# PSM_components_REV_C.net
KiCad netlist of a schematic drawn in Altium Designer
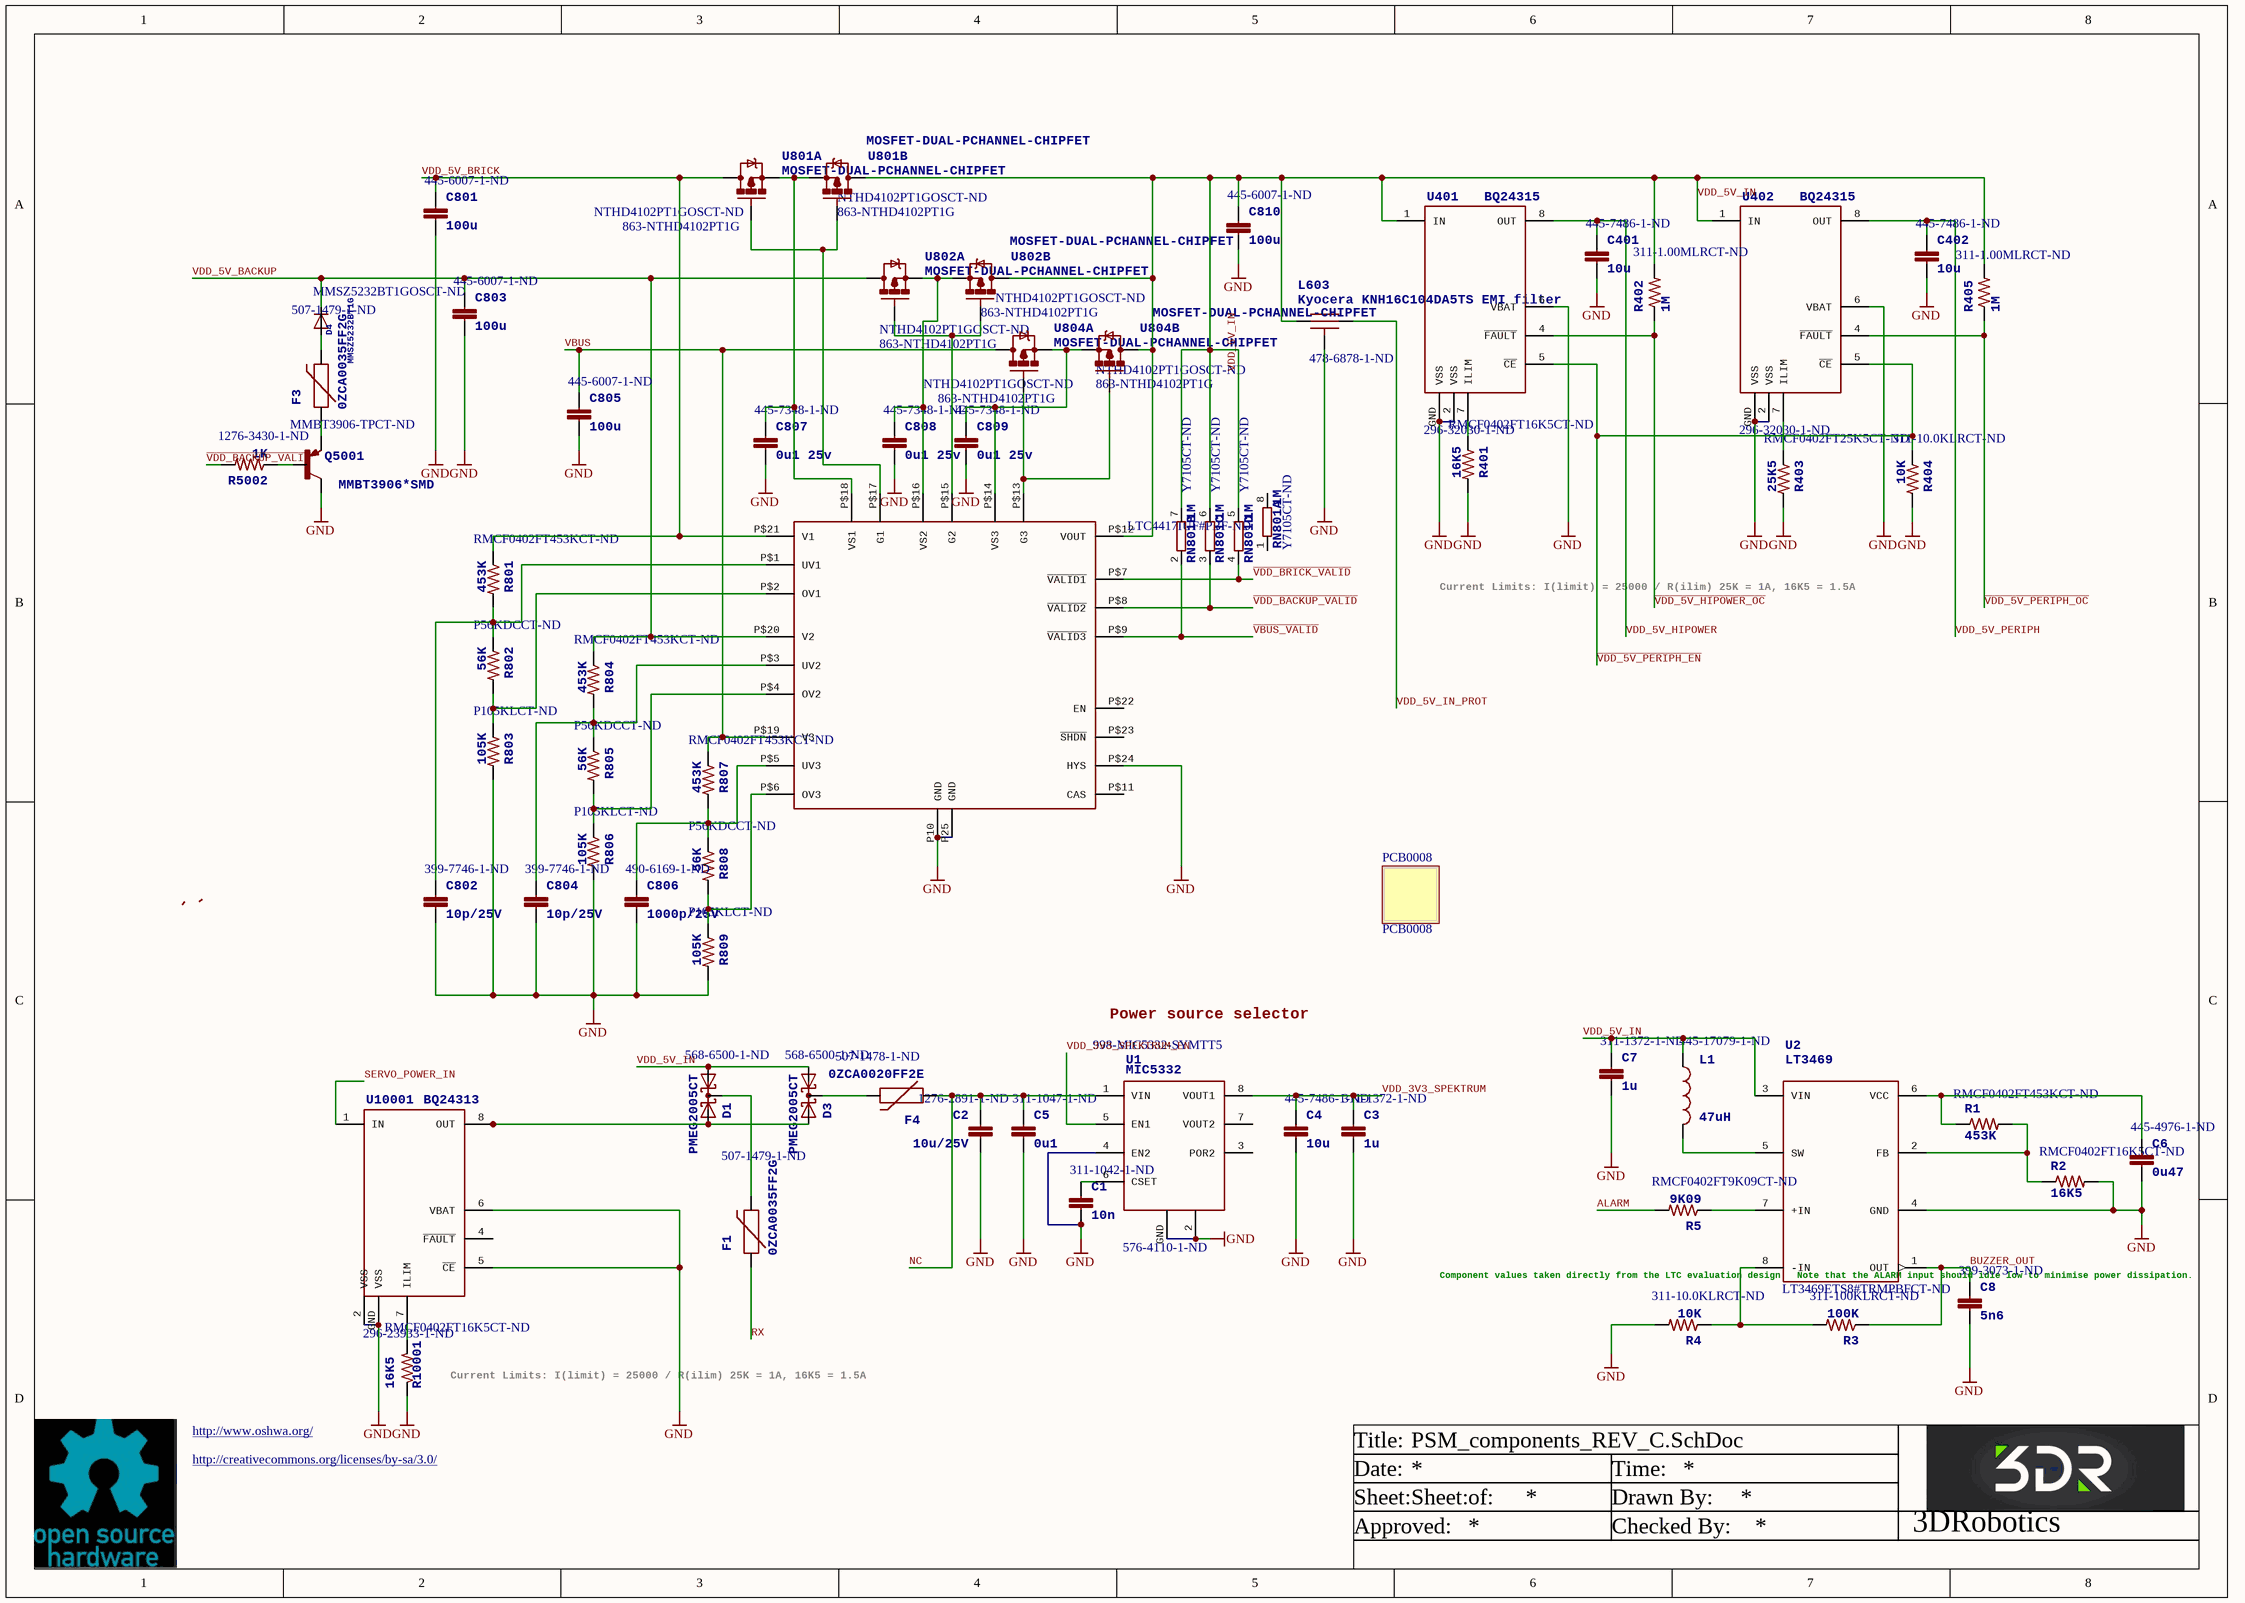
[diagram p0: PSM_components_REV_C.SchDoc]

(export (version "E")
  (design (tool "Eeschema 10.0.6"))
  (components
    (comp (ref "C1")
      (value "10n")
      (footprint "0402-CAP")
      (description "CAP CER 10000PF 16V 10% X7R 0402")
      (fields
        (field (name "PARTNO") "CC0402KRX7R7BB103")
        (field (name "SUPPLIER PART NUMBER 1") "311-1042-1-ND")
        (field (name "3DR_PARTNO") "ECM0711")
      )
      (libsource (lib "pixhawk2") (part "CAP0402"))
    )
    (comp (ref "C2")
      (value "10u/25V")
      (footprint "0805-CAP")
      (description "CAP CER 10UF 25V 10% X5R 0805")
      (fields
        (field (name "PARTNO") "CL21A106KAYNNNE")
        (field (name "SUPPLIER PART NUMBER 1") "1276-2891-1-ND")
        (field (name "3DR_PARTNO") "ECM0714")
      )
      (libsource (lib "pixhawk2") (part "CAP0805"))
    )
    (comp (ref "C3")
      (value "1u")
      (footprint "0603-CAP")
      (description "CAP CER 1UF 16V Y5V 0603")
      (fields
        (field (name "PARTNO") "CC0603ZRY5V7BB105")
        (field (name "SUPPLIER PART NUMBER 1") "311-1372-1-ND")
        (field (name "3DR_PARTNO") "ECM0705")
      )
      (libsource (lib "pixhawk2") (part "CAP0603"))
    )
    (comp (ref "C4")
      (value "10u")
      (footprint "0603-CAP")
      (description "CAP CER 10UF 10V 10% X5R 0603")
      (fields
        (field (name "PARTNO") "C1608X5R1A106K080AC")
        (field (name "SUPPLIER PART NUMBER 1") "445-7486-1-ND")
        (field (name "3DR_PARTNO") "ECM0712")
      )
      (libsource (lib "pixhawk2") (part "CAP0603"))
    )
    (comp (ref "C5")
      (value "0u1")
      (footprint "0402-CAP")
      (description "CAP CER 0.1UF 16V Y5V 0402")
      (fields
        (field (name "PARTNO") "CC0402ZRY5V7BB104")
        (field (name "SUPPLIER PART NUMBER 1") "311-1047-1-ND")
        (field (name "3DR_PARTNO") "ECM0700")
      )
      (libsource (lib "pixhawk2") (part "CAP0402"))
    )
    (comp (ref "C6")
      (value "0u47")
      (footprint "0402-CAP")
      (description "CAP CER 0.47UF 16V 10% X5R 0402")
      (fields
        (field (name "PARTNO") "C1005X5R1C474K050BC")
        (field (name "SUPPLIER PART NUMBER 1") "445-4976-1-ND")
        (field (name "3DR_PARTNO") "ECM0704")
      )
      (libsource (lib "pixhawk2") (part "CAP0402"))
    )
    (comp (ref "C7")
      (value "1u")
      (footprint "0603-CAP")
      (description "CAP CER 1UF 16V Y5V 0603")
      (fields
        (field (name "PARTNO") "CC0603ZRY5V7BB105")
        (field (name "SUPPLIER PART NUMBER 1") "311-1372-1-ND")
        (field (name "3DR_PARTNO") "ECM0705")
      )
      (libsource (lib "pixhawk2") (part "CAP0603"))
    )
    (comp (ref "C8")
      (value "5n6")
      (footprint "0402-CAP")
      (description "CAP CER 5600PF 50V 10% X7R 0402")
      (fields
        (field (name "PARTNO") "C0402C562K5RACTU")
        (field (name "SUPPLIER PART NUMBER 1") "399-3073-1-ND")
        (field (name "3DR_PARTNO") "ECM0535")
      )
      (libsource (lib "pixhawk2") (part "CAP0402"))
    )
    (comp (ref "C401")
      (value "10u")
      (footprint "0603-CAP")
      (description "CAP CER 10UF 10V 10% X5R 0603")
      (fields
        (field (name "PARTNO") "C1608X5R1A106K080AC")
        (field (name "SUPPLIER PART NUMBER 1") "445-7486-1-ND")
        (field (name "3DR_PARTNO") "ECM0712")
      )
      (libsource (lib "pixhawk2") (part "CAP0603"))
    )
    (comp (ref "C402")
      (value "10u")
      (footprint "0603-CAP")
      (description "CAP CER 10UF 10V 10% X5R 0603")
      (fields
        (field (name "PARTNO") "C1608X5R1A106K080AC")
        (field (name "SUPPLIER PART NUMBER 1") "445-7486-1-ND")
        (field (name "3DR_PARTNO") "ECM0712")
      )
      (libsource (lib "pixhawk2") (part "CAP0603"))
    )
    (comp (ref "C801")
      (value "100u")
      (footprint "1206-CAP")
      (description "CAP CER 100UF 10V 20% X5R 1206")
      (fields
        (field (name "PARTNO") "C3216X5R1A107M160AC")
        (field (name "SUPPLIER PART NUMBER 1") "445-6007-1-ND")
        (field (name "3DR_PARTNO") "ECM0716")
      )
      (libsource (lib "pixhawk2") (part "CAP1206"))
    )
    (comp (ref "C802")
      (value "10p/25V")
      (footprint "0402-CAP")
      (description "CAP CER 10PF 25V 5% NP0 0402")
      (fields
        (field (name "PARTNO") "C0402C100J3GACTU")
        (field (name "SUPPLIER PART NUMBER 1") "399-7746-1-ND")
        (field (name "3DR_PARTNO") "ECM0718")
      )
      (libsource (lib "pixhawk2") (part "CAP0402"))
    )
    (comp (ref "C803")
      (value "100u")
      (footprint "1206-CAP")
      (description "CAP CER 100UF 10V 20% X5R 1206")
      (fields
        (field (name "PARTNO") "C3216X5R1A107M160AC")
        (field (name "SUPPLIER PART NUMBER 1") "445-6007-1-ND")
        (field (name "3DR_PARTNO") "ECM0716")
      )
      (libsource (lib "pixhawk2") (part "CAP1206"))
    )
    (comp (ref "C804")
      (value "10p/25V")
      (footprint "0402-CAP")
      (description "CAP CER 10PF 25V 5% NP0 0402")
      (fields
        (field (name "PARTNO") "C0402C100J3GACTU")
        (field (name "SUPPLIER PART NUMBER 1") "399-7746-1-ND")
        (field (name "3DR_PARTNO") "ECM0718")
      )
      (libsource (lib "pixhawk2") (part "CAP0402"))
    )
    (comp (ref "C805")
      (value "100u")
      (footprint "1206-CAP")
      (description "CAP CER 100UF 10V 20% X5R 1206")
      (fields
        (field (name "PARTNO") "C3216X5R1A107M160AC")
        (field (name "SUPPLIER PART NUMBER 1") "445-6007-1-ND")
        (field (name "3DR_PARTNO") "ECM0716")
      )
      (libsource (lib "pixhawk2") (part "CAP1206"))
    )
    (comp (ref "C806")
      (value "1000p/25V")
      (footprint "0402-CAP")
      (description "CAP CER 1000PF 25V 5% NP0 0402")
      (fields
        (field (name "PARTNO") "GRM1555C1E102JA01D")
        (field (name "SUPPLIER PART NUMBER 1") "490-6169-1-ND")
        (field (name "3DR_PARTNO") "ECM0717")
      )
      (libsource (lib "pixhawk2") (part "CAP0402"))
    )
    (comp (ref "C807")
      (value "0u1 25v")
      (footprint "0402-CAP")
      (description "CAP CER 0.1UF 25V 10% X7R 0402")
      (fields
        (field (name "PARTNO") "C1005X7R1E104K050BB")
        (field (name "SUPPLIER PART NUMBER 1") "445-7348-1-ND")
        (field (name "3DR_PARTNO") "ECM0701")
      )
      (libsource (lib "pixhawk2") (part "CAP0402"))
    )
    (comp (ref "C808")
      (value "0u1 25v")
      (footprint "0402-CAP")
      (description "CAP CER 0.1UF 25V 10% X7R 0402")
      (fields
        (field (name "PARTNO") "C1005X7R1E104K050BB")
        (field (name "SUPPLIER PART NUMBER 1") "445-7348-1-ND")
        (field (name "3DR_PARTNO") "ECM0701")
      )
      (libsource (lib "pixhawk2") (part "CAP0402"))
    )
    (comp (ref "C809")
      (value "0u1 25v")
      (footprint "0402-CAP")
      (description "CAP CER 0.1UF 25V 10% X7R 0402")
      (fields
        (field (name "PARTNO") "C1005X7R1E104K050BB")
        (field (name "SUPPLIER PART NUMBER 1") "445-7348-1-ND")
        (field (name "3DR_PARTNO") "ECM0701")
      )
      (libsource (lib "pixhawk2") (part "CAP0402"))
    )
    (comp (ref "C810")
      (value "100u")
      (footprint "1206-CAP")
      (description "CAP CER 100UF 10V 20% X5R 1206")
      (fields
        (field (name "PARTNO") "C3216X5R1A107M160AC")
        (field (name "SUPPLIER PART NUMBER 1") "445-6007-1-ND")
        (field (name "3DR_PARTNO") "ECM0716")
      )
      (libsource (lib "pixhawk2") (part "CAP1206"))
    )
    (comp (ref "D1")
      (value "PMEG2005CT")
      (footprint "SOT23-3")
      (description "DIODE SCHOTTKY 20V 500MA TO236AB")
      (fields (field (name "SUPPLIER PART NUMBER 1") "568-6500-1-ND") (field (name "3DR_PARTNO") "ECM0838"))
      (libsource (lib "pixhawk2") (part "PMEG2005CT"))
    )
    (comp (ref "D3")
      (value "PMEG2005CT")
      (footprint "SOT23-3")
      (description "DIODE SCHOTTKY 20V 500MA TO236AB")
      (fields (field (name "SUPPLIER PART NUMBER 1") "568-6500-1-ND") (field (name "3DR_PARTNO") "ECM0838"))
      (libsource (lib "pixhawk2") (part "PMEG2005CT"))
    )
    (comp (ref "D4")
      (value "MMSZ5232BT1G")
      (footprint "SOD-123")
      (description "DIODE ZENER 5.6V 500MW SOD123")
      (fields
        (field (name "SUPPLIER PART NUMBER 1") "MMSZ5232BT1GOSCT-ND")
        (field (name "3DR_PARTNO") "ECM0536")
      )
      (libsource (lib "adafruit") (part "DIODESOD-123"))
    )
    (comp (ref "F1")
      (value "0ZCA0035FF2G")
      (footprint "PTC-1206")
      (description "PTC RESTTBLE 0.35A 16V CHIP 1206")
      (fields (field (name "SUPPLIER PART NUMBER 1") "507-1479-1-ND") (field (name "3DR_PARTNO") "ECM0802"))
      (libsource (lib "pixhawk2") (part "PTCSMD"))
    )
    (comp (ref "F3")
      (value "0ZCA0035FF2G")
      (footprint "PTC-1206")
      (description "PTC RESTTBLE 0.35A 16V CHIP 1206")
      (fields (field (name "SUPPLIER PART NUMBER 1") "507-1479-1-ND") (field (name "3DR_PARTNO") "ECM0802"))
      (libsource (lib "pixhawk2") (part "PTCSMD"))
    )
    (comp (ref "F4")
      (value "0ZCA0020FF2E")
      (footprint "PTC-1206")
      (description "PTC RESTTBLE 0.20A 30V CHIP 1206")
      (fields (field (name "SUPPLIER PART NUMBER 1") "507-1478-1-ND") (field (name "3DR_PARTNO") "ECM0537"))
      (libsource (lib "pixhawk2") (part "PTCSMD"))
    )
    (comp (ref "L1")
      (value "47uH")
      (footprint "0805-IND")
      (description "FIXED IND 47UH 170MA 4.81 OHM")
      (fields
        (field (name "PARTNO") "MLZ2012M470W")
        (field (name "SUPPLIER PART NUMBER 1") "445-17079-1-ND")
        (field (name "3DR_PARTNO") "ECM0814")
      )
      (libsource (lib "pixhawk2") (part "INDUCTOR0805"))
    )
    (comp (ref "L603")
      (value "Kyocera KNH16C104DA5TS EMI filter")
      (footprint "KYOCERA-KNH16-DA")
      (description "FILTER CAP 0.1UF 2A 25V 0603")
      (fields
        (field (name "SUPPLIER PART NUMBER 1") "478-6878-1-ND")
        (field (name "3DR_PARTNO") "ECM0719")
        (field (name "PARTNO") "KNH16C104DA5TS")
      )
      (libsource (lib "pixhawk2") (part "KNH16C104DA5TS"))
    )
    (comp (ref "PCB0008") (value "PCB0008") (libsource (lib "lib_pixhawk") (part "PCB_0008")))
    (comp (ref "Q5001")
      (value "MMBT3906*SMD")
      (footprint "SOT23-BEC")
      (description "TRANS SS PNP 40V 300MW SOT23")
      (fields
        (field (name "SUPPLIER PART NUMBER 1") "MMBT3906-TPCT-ND")
        (field (name "3DR_PARTNO") "ECM0539")
      )
      (libsource (lib "transistor-pnp") (part "MMBT3906*SMD"))
    )
    (comp (ref "R1")
      (value "453K")
      (footprint "0402-RES")
      (description "RES 453K OHM 1/16W 1% 0402")
      (fields
        (field (name "PARTNO") "RMCF0402FT453K")
        (field (name "SUPPLIER PART NUMBER 1") "RMCF0402FT453KCT-ND")
        (field (name "3DR_PARTNO") "ECM0822")
      )
      (libsource (lib "pixhawk2") (part "RESISTOR0402-RES"))
    )
    (comp (ref "R2")
      (value "16K5")
      (footprint "0402-RES")
      (description "RES 16.5K OHM 1/16W 1% 0402")
      (fields
        (field (name "PARTNO") "RMCF0402FT16K5")
        (field (name "SUPPLIER PART NUMBER 1") "RMCF0402FT16K5CT-ND")
        (field (name "3DR_PARTNO") "ECM0812")
      )
      (libsource (lib "pixhawk2") (part "RESISTOR0402-RES"))
    )
    (comp (ref "R3")
      (value "100K")
      (footprint "0402-RES")
      (description "RES 100K OHM 1/16W 1% 0402 SMD")
      (fields
        (field (name "PARTNO") "RC0402FR-07100KL")
        (field (name "SUPPLIER PART NUMBER 1") "311-100KLRCT-ND")
        (field (name "3DR_PARTNO") "ECM0818")
      )
      (libsource (lib "pixhawk2") (part "RESISTOR0402-RES"))
    )
    (comp (ref "R4")
      (value "10K")
      (footprint "0402-RES")
      (description "RES 10K OHM 1/16W 1% 0402 SMD")
      (fields
        (field (name "PARTNO") "RC0402FR-0710KL")
        (field (name "SUPPLIER PART NUMBER 1") "311-10.0KLRCT-ND")
        (field (name "3DR_PARTNO") "ECM0800")
      )
      (libsource (lib "pixhawk2") (part "RESISTOR0402-RES"))
    )
    (comp (ref "R5")
      (value "9K09")
      (footprint "0402-RES")
      (description "RES 9.09K OHM 1/16W 1% 0402")
      (fields
        (field (name "PARTNO") "RMCF0402FT9K09")
        (field (name "SUPPLIER PART NUMBER 1") "RMCF0402FT9K09CT-ND")
        (field (name "3DR_PARTNO") "ECM0540")
      )
      (libsource (lib "pixhawk2") (part "RESISTOR0402-RES"))
    )
    (comp (ref "R401")
      (value "16K5")
      (footprint "0402-RES")
      (description "RES 16.5K OHM 1/16W 1% 0402")
      (fields
        (field (name "PARTNO") "RMCF0402FT16K5")
        (field (name "SUPPLIER PART NUMBER 1") "RMCF0402FT16K5CT-ND")
        (field (name "3DR_PARTNO") "ECM0812")
      )
      (libsource (lib "pixhawk2") (part "RESISTOR0402-RES"))
    )
    (comp (ref "R402")
      (value "1M")
      (footprint "0402-RES")
      (description "RES 1M OHM 1/16W 1% 0402 SMD")
      (fields
        (field (name "PARTNO") "RC0402FR-071ML")
        (field (name "SUPPLIER PART NUMBER 1") "311-1.00MLRCT-ND")
        (field (name "3DR_PARTNO") "ECM0806")
      )
      (libsource (lib "pixhawk2") (part "RESISTOR0402-RES"))
    )
    (comp (ref "R403")
      (value "25K5")
      (footprint "0402-RES")
      (description "RES 25.5K OHM 1/16W 1% 0402")
      (fields
        (field (name "PARTNO") "RMCF0402FT25K5")
        (field (name "SUPPLIER PART NUMBER 1") "RMCF0402FT25K5CT-ND")
        (field (name "3DR_PARTNO") "ECM0813")
      )
      (libsource (lib "pixhawk2") (part "RESISTOR0402-RES"))
    )
    (comp (ref "R404")
      (value "10K")
      (footprint "0402-RES")
      (description "RES 10K OHM 1/16W 1% 0402 SMD")
      (fields
        (field (name "PARTNO") "RC0402FR-0710KL")
        (field (name "SUPPLIER PART NUMBER 1") "311-10.0KLRCT-ND")
        (field (name "3DR_PARTNO") "ECM0800")
      )
      (libsource (lib "pixhawk2") (part "RESISTOR0402-RES"))
    )
    (comp (ref "R405")
      (value "1M")
      (footprint "0402-RES")
      (description "RES 1M OHM 1/16W 1% 0402 SMD")
      (fields
        (field (name "PARTNO") "RC0402FR-071ML")
        (field (name "SUPPLIER PART NUMBER 1") "311-1.00MLRCT-ND")
        (field (name "3DR_PARTNO") "ECM0806")
      )
      (libsource (lib "pixhawk2") (part "RESISTOR0402-RES"))
    )
    (comp (ref "R801")
      (value "453K")
      (footprint "0402-RES")
      (description "RES 453K OHM 1/16W 1% 0402")
      (fields
        (field (name "PARTNO") "RMCF0402FT453K")
        (field (name "SUPPLIER PART NUMBER 1") "RMCF0402FT453KCT-ND")
        (field (name "3DR_PARTNO") "ECM0822")
      )
      (libsource (lib "pixhawk2") (part "RESISTOR0402-RES"))
    )
    (comp (ref "R802")
      (value "56K")
      (footprint "0402-RES")
      (description "RES 56K OHM 1/16W .1% 0402 SMD")
      (fields
        (field (name "PARTNO") "ERA-2AEB563X")
        (field (name "SUPPLIER PART NUMBER 1") "P56KDCCT-ND")
        (field (name "3DR_PARTNO") "ECM0815")
      )
      (libsource (lib "pixhawk2") (part "RESISTOR0402-RES"))
    )
    (comp (ref "R803")
      (value "105K")
      (footprint "0402-RES")
      (description "RES 105K OHM 1/10W 1% 0402 SMD")
      (fields
        (field (name "PARTNO") "ERJ-2RKF1053X")
        (field (name "SUPPLIER PART NUMBER 1") "P105KLCT-ND")
        (field (name "3DR_PARTNO") "ECM0819")
      )
      (libsource (lib "pixhawk2") (part "RESISTOR0402-RES"))
    )
    (comp (ref "R804")
      (value "453K")
      (footprint "0402-RES")
      (description "RES 453K OHM 1/16W 1% 0402")
      (fields
        (field (name "PARTNO") "RMCF0402FT453K")
        (field (name "SUPPLIER PART NUMBER 1") "RMCF0402FT453KCT-ND")
        (field (name "3DR_PARTNO") "ECM0822")
      )
      (libsource (lib "pixhawk2") (part "RESISTOR0402-RES"))
    )
    (comp (ref "R805")
      (value "56K")
      (footprint "0402-RES")
      (description "RES 56K OHM 1/16W .1% 0402 SMD")
      (fields
        (field (name "PARTNO") "ERA-2AEB563X")
        (field (name "SUPPLIER PART NUMBER 1") "P56KDCCT-ND")
        (field (name "3DR_PARTNO") "ECM0815")
      )
      (libsource (lib "pixhawk2") (part "RESISTOR0402-RES"))
    )
    (comp (ref "R806")
      (value "105K")
      (footprint "0402-RES")
      (description "RES 105K OHM 1/10W 1% 0402 SMD")
      (fields
        (field (name "PARTNO") "ERJ-2RKF1053X")
        (field (name "SUPPLIER PART NUMBER 1") "P105KLCT-ND")
        (field (name "3DR_PARTNO") "ECM0819")
      )
      (libsource (lib "pixhawk2") (part "RESISTOR0402-RES"))
    )
    (comp (ref "R807")
      (value "453K")
      (footprint "0402-RES")
      (description "RES 453K OHM 1/16W 1% 0402")
      (fields
        (field (name "PARTNO") "RMCF0402FT453K")
        (field (name "SUPPLIER PART NUMBER 1") "RMCF0402FT453KCT-ND")
        (field (name "3DR_PARTNO") "ECM0822")
      )
      (libsource (lib "pixhawk2") (part "RESISTOR0402-RES"))
    )
    (comp (ref "R808")
      (value "56K")
      (footprint "0402-RES")
      (description "RES 56K OHM 1/16W .1% 0402 SMD")
      (fields
        (field (name "PARTNO") "ERA-2AEB563X")
        (field (name "SUPPLIER PART NUMBER 1") "P56KDCCT-ND")
        (field (name "3DR_PARTNO") "ECM0815")
      )
      (libsource (lib "pixhawk2") (part "RESISTOR0402-RES"))
    )
    (comp (ref "R809")
      (value "105K")
      (footprint "0402-RES")
      (description "RES 105K OHM 1/10W 1% 0402 SMD")
      (fields
        (field (name "PARTNO") "ERJ-2RKF1053X")
        (field (name "SUPPLIER PART NUMBER 1") "P105KLCT-ND")
        (field (name "3DR_PARTNO") "ECM0819")
      )
      (libsource (lib "pixhawk2") (part "RESISTOR0402-RES"))
    )
    (comp (ref "R5002")
      (value "1K")
      (footprint "0402-RES")
      (description "RES 1K OHM 1/16W 1% 0402")
      (fields
        (field (name "PARTNO") "RC1005F102CS")
        (field (name "SUPPLIER PART NUMBER 1") "1276-3430-1-ND")
        (field (name "3DR_PARTNO") "ECM0804")
      )
      (libsource (lib "pixhawk2") (part "RESISTOR0402-RES"))
    )
    (comp (ref "R10001")
      (value "16K5")
      (footprint "0402-RES")
      (description "RES 16.5K OHM 1/16W 1% 0402")
      (fields
        (field (name "SUPPLIER PART NUMBER 1") "RMCF0402FT16K5CT-ND")
        (field (name "3DR_PARTNO") "ECM0812")
      )
      (libsource (lib "pixhawk2") (part "RESISTOR0402-RES"))
    )
    (comp (ref "RN801")
      (value "1M")
      (footprint "EXB28V")
      (description "RES ARRAY 1M OHM 4 RES 0804")
      (fields
        (field (name "PARTNO") "EXB-28V105JX")
        (field (name "SUPPLIER PART NUMBER 1") "Y7105CT-ND")
        (field (name "3DR_PARTNO") "ECM0805")
      )
      (libsource (lib "resistor-dil") (part "4R-NEXB28V"))
    )
    (comp (ref "U1")
      (value "MIC5332")
      (footprint "MLF-8-EPAD")
      (description "IC REG LDO 3.3V 0.3A 8TMLF")
      (fields
        (field (name "SUPPLIER PART NUMBER 1") "576-4110-1-ND")
        (field (name "SUPPLIER PART NUMBER 2") "998-MIC5332-SYMTT5")
        (field (name "3DR_PARTNO") "ECM0832")
      )
      (libsource (lib "pixhawk2") (part "MIC5332"))
    )
    (comp (ref "U2")
      (value "LT3469")
      (footprint "SOT23-8")
      (description "IC AMP DVR W/REG 1.3MHZ TSOT23-8")
      (fields
        (field (name "SUPPLIER PART NUMBER 1") "LT3469ETS8#TRMPBFCT-ND")
        (field (name "3DR_PARTNO") "ECM0829")
      )
      (libsource (lib "pixhawk2") (part "LT3469"))
    )
    (comp (ref "U401")
      (value "BQ24315")
      (footprint "pixhawk2:QFN8-DSG")
      (description "IC LI+ CHARGER FRONT END 8SON")
      (fields (field (name "SUPPLIER PART NUMBER 1") "296-32030-1-ND") (field (name "3DR_PARTNO") "ECM0541"))
      (libsource (lib "pixhawk2") (part "BQ24315"))
    )
    (comp (ref "U402")
      (value "BQ24315")
      (footprint "pixhawk2:QFN8-DSG")
      (description "IC LI+ CHARGER FRONT END 8SON")
      (fields (field (name "SUPPLIER PART NUMBER 1") "296-32030-1-ND") (field (name "3DR_PARTNO") "ECM0541"))
      (libsource (lib "pixhawk2") (part "BQ24315"))
    )
    (comp (ref "U801")
      (value "MOSFET-DUAL-PCHANNEL-CHIPFET")
      (footprint "1206-8")
      (description "MOSFET 2P-CH 20V 2.9A CHIPFET")
      (fields
        (field (name "SUPPLIER PART NUMBER 1") "NTHD4102PT1GOSCT-ND")
        (field (name "SUPPLIER PART NUMBER 2") "863-NTHD4102PT1G")
        (field (name "3DR_PARTNO") "EMC0901")
      )
      (libsource (lib "pixhawk2") (part "MOSFET-DUAL-PCHANNEL-CHIPFET"))
    )
    (comp (ref "U802")
      (value "MOSFET-DUAL-PCHANNEL-CHIPFET")
      (footprint "1206-8")
      (description "MOSFET 2P-CH 20V 2.9A CHIPFET")
      (fields
        (field (name "SUPPLIER PART NUMBER 1") "NTHD4102PT1GOSCT-ND")
        (field (name "SUPPLIER PART NUMBER 2") "863-NTHD4102PT1G")
        (field (name "3DR_PARTNO") "EMC0901")
      )
      (libsource (lib "") (part "MOSFET-DUAL-PCHANNEL-CHIPFET_1"))
    )
    (comp (ref "U803")
      (value "LTC4417")
      (footprint "pixhawk2:MO-220")
      (description "IC OR CTRLR SRC SELECT 24QFN")
      (fields
        (field (name "SUPPLIER PART NUMBER 1") "LTC4417IUF#PBF-ND")
        (field (name "3DR_PARTNO") "ECM0830")
      )
      (libsource (lib "pixhawk2") (part "LTC4117"))
    )
    (comp (ref "U804")
      (value "MOSFET-DUAL-PCHANNEL-CHIPFET")
      (footprint "1206-8")
      (description "MOSFET 2P-CH 20V 2.9A CHIPFET")
      (fields
        (field (name "SUPPLIER PART NUMBER 1") "NTHD4102PT1GOSCT-ND")
        (field (name "SUPPLIER PART NUMBER 2") "863-NTHD4102PT1G")
        (field (name "3DR_PARTNO") "EMC0901")
      )
      (libsource (lib "") (part "MOSFET-DUAL-PCHANNEL-CHIPFET_1"))
    )
    (comp (ref "U10001")
      (value "BQ24313")
      (footprint "power:QFN8-DSG")
      (description "IC LI+ CHARGER FRONT END 8-SON")
      (fields (field (name "SUPPLIER PART NUMBER 1") "296-23933-1-ND") (field (name "3DR_PARTNO") "ECM0824"))
      (libsource (lib "pixhawk2") (part "BQ24313"))
    )
  )
  (nets
    (net (code "1") (name "/ALARM") (class "Default")
      (node (ref "R5") (pin "P$2") (pinfunction "2_P$2") (pintype "passive"))
    )
    (net (code "2") (name "/BUZZER_OUT") (class "Default")
      (node (ref "C8") (pin "P$1") (pinfunction "1_P$1") (pintype "passive"))
      (node (ref "R3") (pin "P$1") (pinfunction "1_P$1") (pintype "passive"))
      (node (ref "U2") (pin "1") (pinfunction "OUT_1") (pintype "output"))
    )
    (net (code "3") (name "/NC") (class "Default")
      (node (ref "C2") (pin "P$1") (pinfunction "1_P$1") (pintype "passive"))
      (node (ref "C5") (pin "P$1") (pinfunction "1_P$1") (pintype "passive"))
      (node (ref "F4") (pin "1") (pinfunction "1_1") (pintype "passive"))
      (node (ref "U1") (pin "1") (pinfunction "VIN_1") (pintype "passive"))
    )
    (net (code "4") (name "/RX") (class "Default")
      (node (ref "F1") (pin "1") (pinfunction "1_1") (pintype "passive"))
    )
    (net (code "5") (name "/SERVO_POWER_IN") (class "Default")
      (node (ref "U10001") (pin "1") (pinfunction "IN_1") (pintype "passive"))
    )
    (net (code "6") (name "/VBUS") (class "Default")
      (node (ref "C805") (pin "P$1") (pinfunction "1_P$1") (pintype "passive"))
      (node (ref "R807") (pin "P$1") (pinfunction "1_P$1") (pintype "passive"))
      (node (ref "U803") (pin "P$19") (pinfunction "V3_P$19") (pintype "passive"))
      (node (ref "U804") (pin "P7") (pinfunction "D_P7") (pintype "passive"))
    )
    (net (code "7") (name "/VDD_3V3_SPEKTRUM") (class "Default")
      (node (ref "C3") (pin "P$1") (pinfunction "1_P$1") (pintype "passive"))
      (node (ref "C4") (pin "P$1") (pinfunction "1_P$1") (pintype "passive"))
      (node (ref "U1") (pin "8") (pinfunction "VOUT1_8") (pintype "passive"))
    )
    (net (code "8") (name "/VDD_3V3_SPEKTRUM_EN") (class "Default")
      (node (ref "U1") (pin "5") (pinfunction "EN1_5") (pintype "passive"))
    )
    (net (code "9") (name "/VDD_5V_BACKUP") (class "Default")
      (node (ref "C803") (pin "P$1") (pinfunction "1_P$1") (pintype "passive"))
      (node (ref "D4") (pin "C") (pinfunction "C_C") (pintype "passive"))
      (node (ref "R804") (pin "P$1") (pinfunction "1_P$1") (pintype "passive"))
      (node (ref "U802") (pin "P7") (pinfunction "D_P7") (pintype "passive"))
      (node (ref "U803") (pin "P$20") (pinfunction "V2_P$20") (pintype "passive"))
    )
    (net (code "10") (name "/VDD_5V_BRICK") (class "Default")
      (node (ref "C801") (pin "P$1") (pinfunction "1_P$1") (pintype "passive"))
      (node (ref "R801") (pin "P$1") (pinfunction "1_P$1") (pintype "passive"))
      (node (ref "U801") (pin "P7") (pinfunction "D_P7") (pintype "passive"))
      (node (ref "U803") (pin "P$21") (pinfunction "V1_P$21") (pintype "passive"))
    )
    (net (code "11") (name "/VDD_5V_HIPOWER") (class "Default")
      (node (ref "C401") (pin "P$1") (pinfunction "1_P$1") (pintype "passive"))
      (node (ref "U401") (pin "8") (pinfunction "OUT_8") (pintype "passive"))
    )
    (net (code "12") (name "/VDD_5V_IN") (class "Default")
      (node (ref "C7") (pin "P$1") (pinfunction "1_P$1") (pintype "passive"))
      (node (ref "C810") (pin "P$1") (pinfunction "1_P$1") (pintype "passive"))
      (node (ref "D1") (pin "1") (pinfunction "A1_1") (pintype "passive"))
      (node (ref "D3") (pin "1") (pinfunction "A1_1") (pintype "passive"))
      (node (ref "L1") (pin "P$1") (pinfunction "1_P$1") (pintype "passive"))
      (node (ref "L603") (pin "P$1") (pinfunction "P$1_P$1") (pintype "passive"))
      (node (ref "R402") (pin "P$2") (pinfunction "2_P$2") (pintype "passive"))
      (node (ref "R405") (pin "P$2") (pinfunction "2_P$2") (pintype "passive"))
      (node (ref "RN801") (pin "5") (pinfunction "2_5") (pintype "passive"))
      (node (ref "RN801") (pin "6") (pinfunction "2_6") (pintype "passive"))
      (node (ref "RN801") (pin "7") (pinfunction "2_7") (pintype "passive"))
      (node (ref "U2") (pin "3") (pinfunction "VIN_3") (pintype "power_in"))
      (node (ref "U401") (pin "1") (pinfunction "IN_1") (pintype "passive"))
      (node (ref "U402") (pin "1") (pinfunction "IN_1") (pintype "passive"))
      (node (ref "U801") (pin "P5") (pinfunction "D_P5") (pintype "passive"))
      (node (ref "U802") (pin "P5") (pinfunction "D_P5") (pintype "passive"))
      (node (ref "U803") (pin "P$12") (pinfunction "VOUT_P$12") (pintype "passive"))
      (node (ref "U804") (pin "P5") (pinfunction "D_P5") (pintype "passive"))
    )
    (net (code "13") (name "/VDD_5V_IN_PROT") (class "Default")
      (node (ref "L603") (pin "P$2") (pinfunction "P$2_P$2") (pintype "passive"))
    )
    (net (code "14") (name "/VDD_5V_PERIPH") (class "Default")
      (node (ref "C402") (pin "P$1") (pinfunction "1_P$1") (pintype "passive"))
      (node (ref "U402") (pin "8") (pinfunction "OUT_8") (pintype "passive"))
    )
    (net (code "15") (name "/~{VBUS_VALID}") (class "Default")
      (node (ref "RN801") (pin "2") (pinfunction "1_2") (pintype "passive"))
      (node (ref "U803") (pin "P$9") (pinfunction "~{VALID3}_P$9") (pintype "passive"))
    )
    (net (code "16") (name "/~{VDD_5V_HIPOWER_OC}") (class "Default")
      (node (ref "R402") (pin "P$1") (pinfunction "1_P$1") (pintype "passive"))
      (node (ref "U401") (pin "4") (pinfunction "~{FAULT}_4") (pintype "passive"))
    )
    (net (code "17") (name "/~{VDD_5V_PERIPH_EN}") (class "Default")
      (node (ref "R404") (pin "P$1") (pinfunction "1_P$1") (pintype "passive"))
      (node (ref "U401") (pin "5") (pinfunction "~{CE}_5") (pintype "passive"))
      (node (ref "U402") (pin "5") (pinfunction "~{CE}_5") (pintype "passive"))
    )
    (net (code "18") (name "/~{VDD_5V_PERIPH_OC}") (class "Default")
      (node (ref "R405") (pin "P$1") (pinfunction "1_P$1") (pintype "passive"))
      (node (ref "U402") (pin "4") (pinfunction "~{FAULT}_4") (pintype "passive"))
    )
    (net (code "19") (name "/~{VDD_BACKUP_VALID}") (class "Default")
      (node (ref "R5002") (pin "P$2") (pinfunction "2_P$2") (pintype "passive"))
      (node (ref "RN801") (pin "3") (pinfunction "1_3") (pintype "passive"))
      (node (ref "U803") (pin "P$8") (pinfunction "~{VALID2}_P$8") (pintype "passive"))
    )
    (net (code "20") (name "/~{VDD_BRICK_VALID}") (class "Default")
      (node (ref "RN801") (pin "4") (pinfunction "1_4") (pintype "passive"))
      (node (ref "U803") (pin "P$7") (pinfunction "~{VALID1}_P$7") (pintype "passive"))
    )
    (net (code "21") (name "GND") (class "Default")
      (node (ref "C1") (pin "P$2") (pinfunction "2_P$2") (pintype "passive"))
      (node (ref "C2") (pin "P$2") (pinfunction "2_P$2") (pintype "passive"))
      (node (ref "C3") (pin "P$2") (pinfunction "2_P$2") (pintype "passive"))
      (node (ref "C4") (pin "P$2") (pinfunction "2_P$2") (pintype "passive"))
      (node (ref "C401") (pin "P$2") (pinfunction "2_P$2") (pintype "passive"))
      (node (ref "C402") (pin "P$2") (pinfunction "2_P$2") (pintype "passive"))
      (node (ref "C5") (pin "P$2") (pinfunction "2_P$2") (pintype "passive"))
      (node (ref "C6") (pin "P$2") (pinfunction "2_P$2") (pintype "passive"))
      (node (ref "C7") (pin "P$2") (pinfunction "2_P$2") (pintype "passive"))
      (node (ref "C8") (pin "P$2") (pinfunction "2_P$2") (pintype "passive"))
      (node (ref "C801") (pin "P$2") (pinfunction "2_P$2") (pintype "passive"))
      (node (ref "C802") (pin "P$2") (pinfunction "2_P$2") (pintype "passive"))
      (node (ref "C803") (pin "P$2") (pinfunction "2_P$2") (pintype "passive"))
      (node (ref "C804") (pin "P$2") (pinfunction "2_P$2") (pintype "passive"))
      (node (ref "C805") (pin "P$2") (pinfunction "2_P$2") (pintype "passive"))
      (node (ref "C806") (pin "P$2") (pinfunction "2_P$2") (pintype "passive"))
      (node (ref "C807") (pin "P$2") (pinfunction "2_P$2") (pintype "passive"))
      (node (ref "C808") (pin "P$2") (pinfunction "2_P$2") (pintype "passive"))
      (node (ref "C809") (pin "P$2") (pinfunction "2_P$2") (pintype "passive"))
      (node (ref "C810") (pin "P$2") (pinfunction "2_P$2") (pintype "passive"))
      (node (ref "L603") (pin "GND") (pinfunction "GND_GND") (pintype "passive"))
      (node (ref "Q5001") (pin "C") (pinfunction "C_C") (pintype "passive"))
      (node (ref "R10001") (pin "P$1") (pinfunction "1_P$1") (pintype "passive"))
      (node (ref "R2") (pin "P$2") (pinfunction "2_P$2") (pintype "passive"))
      (node (ref "R4") (pin "P$2") (pinfunction "2_P$2") (pintype "passive"))
      (node (ref "R401") (pin "P$2") (pinfunction "2_P$2") (pintype "passive"))
      (node (ref "R403") (pin "P$2") (pinfunction "2_P$2") (pintype "passive"))
      (node (ref "R404") (pin "P$2") (pinfunction "2_P$2") (pintype "passive"))
      (node (ref "R803") (pin "P$2") (pinfunction "2_P$2") (pintype "passive"))
      (node (ref "R806") (pin "P$2") (pinfunction "2_P$2") (pintype "passive"))
      (node (ref "R809") (pin "P$2") (pinfunction "2_P$2") (pintype "passive"))
      (node (ref "U1") (pin "2") (pinfunction "GND_2") (pintype "power_in"))
      (node (ref "U1") (pin "4") (pinfunction "EN2_4") (pintype "passive"))
      (node (ref "U1") (pin "GND") (pinfunction "GND_GND") (pintype "power_in"))
      (node (ref "U10001") (pin "2") (pinfunction "VSS_2") (pintype "passive"))
      (node (ref "U10001") (pin "5") (pinfunction "~{CE}_5") (pintype "passive"))
      (node (ref "U10001") (pin "6") (pinfunction "VBAT_6") (pintype "passive"))
      (node (ref "U10001") (pin "GND") (pinfunction "VSS_GND") (pintype "passive"))
      (node (ref "U2") (pin "4") (pinfunction "GND_4") (pintype "power_in"))
      (node (ref "U401") (pin "2") (pinfunction "VSS_2") (pintype "passive"))
      (node (ref "U401") (pin "6") (pinfunction "VBAT_6") (pintype "passive"))
      (node (ref "U401") (pin "GND") (pinfunction "VSS_GND") (pintype "passive"))
      (node (ref "U402") (pin "2") (pinfunction "VSS_2") (pintype "passive"))
      (node (ref "U402") (pin "6") (pinfunction "VBAT_6") (pintype "passive"))
      (node (ref "U402") (pin "GND") (pinfunction "VSS_GND") (pintype "passive"))
      (node (ref "U803") (pin "P$24") (pinfunction "HYS_P$24") (pintype "passive"))
      (node (ref "U803") (pin "P10") (pinfunction "GND_P10") (pintype "passive"))
      (node (ref "U803") (pin "P25") (pinfunction "GND_P25") (pintype "passive"))
    )
    (net (code "22") (name "Net-(C1-1)") (class "Default")
      (node (ref "C1") (pin "P$1") (pinfunction "1_P$1") (pintype "passive"))
      (node (ref "U1") (pin "6") (pinfunction "CSET_6") (pintype "passive"))
    )
    (net (code "23") (name "Net-(C6-1)") (class "Default")
      (node (ref "C6") (pin "P$1") (pinfunction "1_P$1") (pintype "passive"))
      (node (ref "R1") (pin "P$1") (pinfunction "1_P$1") (pintype "passive"))
      (node (ref "U2") (pin "6") (pinfunction "VCC_6") (pintype "passive"))
    )
    (net (code "24") (name "Net-(C802-1)") (class "Default")
      (node (ref "C802") (pin "P$1") (pinfunction "1_P$1") (pintype "passive"))
      (node (ref "R801") (pin "P$2") (pinfunction "2_P$2") (pintype "passive"))
      (node (ref "R802") (pin "P$1") (pinfunction "1_P$1") (pintype "passive"))
      (node (ref "U803") (pin "P$1") (pinfunction "UV1_P$1") (pintype "passive"))
    )
    (net (code "25") (name "Net-(C804-1)") (class "Default")
      (node (ref "C804") (pin "P$1") (pinfunction "1_P$1") (pintype "passive"))
      (node (ref "R804") (pin "P$2") (pinfunction "2_P$2") (pintype "passive"))
      (node (ref "R805") (pin "P$1") (pinfunction "1_P$1") (pintype "passive"))
      (node (ref "U803") (pin "P$3") (pinfunction "UV2_P$3") (pintype "passive"))
    )
    (net (code "26") (name "Net-(C806-1)") (class "Default")
      (node (ref "C806") (pin "P$1") (pinfunction "1_P$1") (pintype "passive"))
      (node (ref "R807") (pin "P$2") (pinfunction "2_P$2") (pintype "passive"))
      (node (ref "R808") (pin "P$1") (pinfunction "1_P$1") (pintype "passive"))
      (node (ref "U803") (pin "P$5") (pinfunction "UV3_P$5") (pintype "passive"))
    )
    (net (code "27") (name "Net-(C807-1)") (class "Default")
      (node (ref "C807") (pin "P$1") (pinfunction "1_P$1") (pintype "passive"))
      (node (ref "U801") (pin "P1") (pinfunction "S_P1") (pintype "passive"))
      (node (ref "U801") (pin "P3") (pinfunction "S_P3") (pintype "passive"))
      (node (ref "U803") (pin "P$18") (pinfunction "VS1_P$18") (pintype "passive"))
    )
    (net (code "28") (name "Net-(C808-1)") (class "Default")
      (node (ref "C808") (pin "P$1") (pinfunction "1_P$1") (pintype "passive"))
      (node (ref "U802") (pin "P1") (pinfunction "S_P1") (pintype "passive"))
      (node (ref "U802") (pin "P3") (pinfunction "S_P3") (pintype "passive"))
      (node (ref "U803") (pin "P$16") (pinfunction "VS2_P$16") (pintype "passive"))
    )
    (net (code "29") (name "Net-(C809-1)") (class "Default")
      (node (ref "C809") (pin "P$1") (pinfunction "1_P$1") (pintype "passive"))
      (node (ref "U803") (pin "P$14") (pinfunction "VS3_P$14") (pintype "passive"))
      (node (ref "U804") (pin "P1") (pinfunction "S_P1") (pintype "passive"))
      (node (ref "U804") (pin "P3") (pinfunction "S_P3") (pintype "passive"))
    )
    (net (code "30") (name "Net-(D1-A2)") (class "Default")
      (node (ref "D1") (pin "2") (pinfunction "A2_2") (pintype "passive"))
      (node (ref "D3") (pin "2") (pinfunction "A2_2") (pintype "passive"))
      (node (ref "U10001") (pin "8") (pinfunction "OUT_8") (pintype "passive"))
    )
    (net (code "31") (name "Net-(D1-CC)") (class "Default")
      (node (ref "D1") (pin "3") (pinfunction "CC_3") (pintype "passive"))
      (node (ref "F1") (pin "2") (pinfunction "2_2") (pintype "passive"))
    )
    (net (code "32") (name "Net-(D3-CC)") (class "Default")
      (node (ref "D3") (pin "3") (pinfunction "CC_3") (pintype "passive"))
      (node (ref "F4") (pin "2") (pinfunction "2_2") (pintype "passive"))
    )
    (net (code "33") (name "Net-(D4-PadA)") (class "Default")
      (node (ref "D4") (pin "A") (pinfunction "A_A") (pintype "passive"))
      (node (ref "F3") (pin "2") (pinfunction "2_2") (pintype "passive"))
    )
    (net (code "34") (name "Net-(F3-Pad1)") (class "Default")
      (node (ref "F3") (pin "1") (pinfunction "1_1") (pintype "passive"))
      (node (ref "Q5001") (pin "E") (pinfunction "E_E") (pintype "passive"))
    )
    (net (code "35") (name "Net-(L1-2)") (class "Default")
      (node (ref "L1") (pin "P$2") (pinfunction "2_P$2") (pintype "passive"))
      (node (ref "U2") (pin "5") (pinfunction "SW_5") (pintype "passive"))
    )
    (net (code "36") (name "Net-(R1-2)") (class "Default")
      (node (ref "R1") (pin "P$2") (pinfunction "2_P$2") (pintype "passive"))
      (node (ref "R2") (pin "P$1") (pinfunction "1_P$1") (pintype "passive"))
      (node (ref "U2") (pin "2") (pinfunction "FB_2") (pintype "passive"))
    )
    (net (code "37") (name "Net-(R3-2)") (class "Default")
      (node (ref "R3") (pin "P$2") (pinfunction "2_P$2") (pintype "passive"))
      (node (ref "R4") (pin "P$1") (pinfunction "1_P$1") (pintype "passive"))
      (node (ref "U2") (pin "8") (pinfunction "-IN_8") (pintype "passive"))
    )
    (net (code "38") (name "Net-(R5-1)") (class "Default")
      (node (ref "R5") (pin "P$1") (pinfunction "1_P$1") (pintype "passive"))
      (node (ref "U2") (pin "7") (pinfunction "+IN_7") (pintype "passive"))
    )
    (net (code "39") (name "Net-(R401-1)") (class "Default")
      (node (ref "R401") (pin "P$1") (pinfunction "1_P$1") (pintype "passive"))
      (node (ref "U401") (pin "7") (pinfunction "ILIM_7") (pintype "passive"))
    )
    (net (code "40") (name "Net-(R403-1)") (class "Default")
      (node (ref "R403") (pin "P$1") (pinfunction "1_P$1") (pintype "passive"))
      (node (ref "U402") (pin "7") (pinfunction "ILIM_7") (pintype "passive"))
    )
    (net (code "41") (name "Net-(R802-2)") (class "Default")
      (node (ref "R802") (pin "P$2") (pinfunction "2_P$2") (pintype "passive"))
      (node (ref "R803") (pin "P$1") (pinfunction "1_P$1") (pintype "passive"))
      (node (ref "U803") (pin "P$2") (pinfunction "OV1_P$2") (pintype "passive"))
    )
    (net (code "42") (name "Net-(R805-2)") (class "Default")
      (node (ref "R805") (pin "P$2") (pinfunction "2_P$2") (pintype "passive"))
      (node (ref "R806") (pin "P$1") (pinfunction "1_P$1") (pintype "passive"))
      (node (ref "U803") (pin "P$4") (pinfunction "OV2_P$4") (pintype "passive"))
    )
    (net (code "43") (name "Net-(R808-2)") (class "Default")
      (node (ref "R808") (pin "P$2") (pinfunction "2_P$2") (pintype "passive"))
      (node (ref "R809") (pin "P$1") (pinfunction "1_P$1") (pintype "passive"))
      (node (ref "U803") (pin "P$6") (pinfunction "OV3_P$6") (pintype "passive"))
    )
    (net (code "44") (name "Net-(R5002-1)") (class "Default")
      (node (ref "Q5001") (pin "B") (pinfunction "B_B") (pintype "passive"))
      (node (ref "R5002") (pin "P$1") (pinfunction "1_P$1") (pintype "passive"))
    )
    (net (code "45") (name "Net-(R10001-2)") (class "Default")
      (node (ref "R10001") (pin "P$2") (pinfunction "2_P$2") (pintype "passive"))
      (node (ref "U10001") (pin "7") (pinfunction "ILIM_7") (pintype "passive"))
    )
    (net (code "46") (name "Net-(U801A-G)") (class "Default")
      (node (ref "U801") (pin "P2") (pinfunction "G_P2") (pintype "passive"))
      (node (ref "U801") (pin "P4") (pinfunction "G_P4") (pintype "passive"))
      (node (ref "U803") (pin "P$17") (pinfunction "G1_P$17") (pintype "passive"))
    )
    (net (code "47") (name "Net-(U802A-G)") (class "Default")
      (node (ref "U802") (pin "P2") (pinfunction "G_P2") (pintype "passive"))
      (node (ref "U802") (pin "P4") (pinfunction "G_P4") (pintype "passive"))
      (node (ref "U803") (pin "P$15") (pinfunction "G2_P$15") (pintype "passive"))
    )
    (net (code "48") (name "Net-(U803-G3)") (class "Default")
      (node (ref "U803") (pin "P$13") (pinfunction "G3_P$13") (pintype "passive"))
      (node (ref "U804") (pin "P2") (pinfunction "G_P2") (pintype "passive"))
      (node (ref "U804") (pin "P4") (pinfunction "G_P4") (pintype "passive"))
    )
    (net (code "49") (name "unconnected-(RN801-Pad1)") (class "Default")
      (node (ref "RN801") (pin "1") (pinfunction "1_1") (pintype "passive"))
    )
    (net (code "50") (name "unconnected-(RN801A-2-Pad8)") (class "Default")
      (node (ref "RN801") (pin "8") (pinfunction "2_8") (pintype "passive"))
    )
    (net (code "51") (name "unconnected-(U1-POR2-Pad3)") (class "Default")
      (node (ref "U1") (pin "3") (pinfunction "POR2_3") (pintype "passive"))
    )
    (net (code "52") (name "unconnected-(U1-VOUT2-Pad7)") (class "Default")
      (node (ref "U1") (pin "7") (pinfunction "VOUT2_7") (pintype "passive"))
    )
    (net (code "53") (name "unconnected-(U803-CAS-PadP$11)") (class "Default")
      (node (ref "U803") (pin "P$11") (pinfunction "CAS_P$11") (pintype "passive"))
    )
    (net (code "54") (name "unconnected-(U803-EN-PadP$22)") (class "Default")
      (node (ref "U803") (pin "P$22") (pinfunction "EN_P$22") (pintype "passive"))
    )
    (net (code "55") (name "unconnected-(U803-~{SHDN}-PadP$23)") (class "Default")
      (node (ref "U803") (pin "P$23") (pinfunction "~{SHDN}_P$23") (pintype "passive"))
    )
    (net (code "56") (name "unconnected-(U10001-~{FAULT}-Pad4)") (class "Default")
      (node (ref "U10001") (pin "4") (pinfunction "~{FAULT}_4") (pintype "passive"))
    )
  )
)
